# FAR_LR1_Remote_Recovery_Schematic_EasyED.net
KiCad netlist of a schematic drawn in EasyEDA
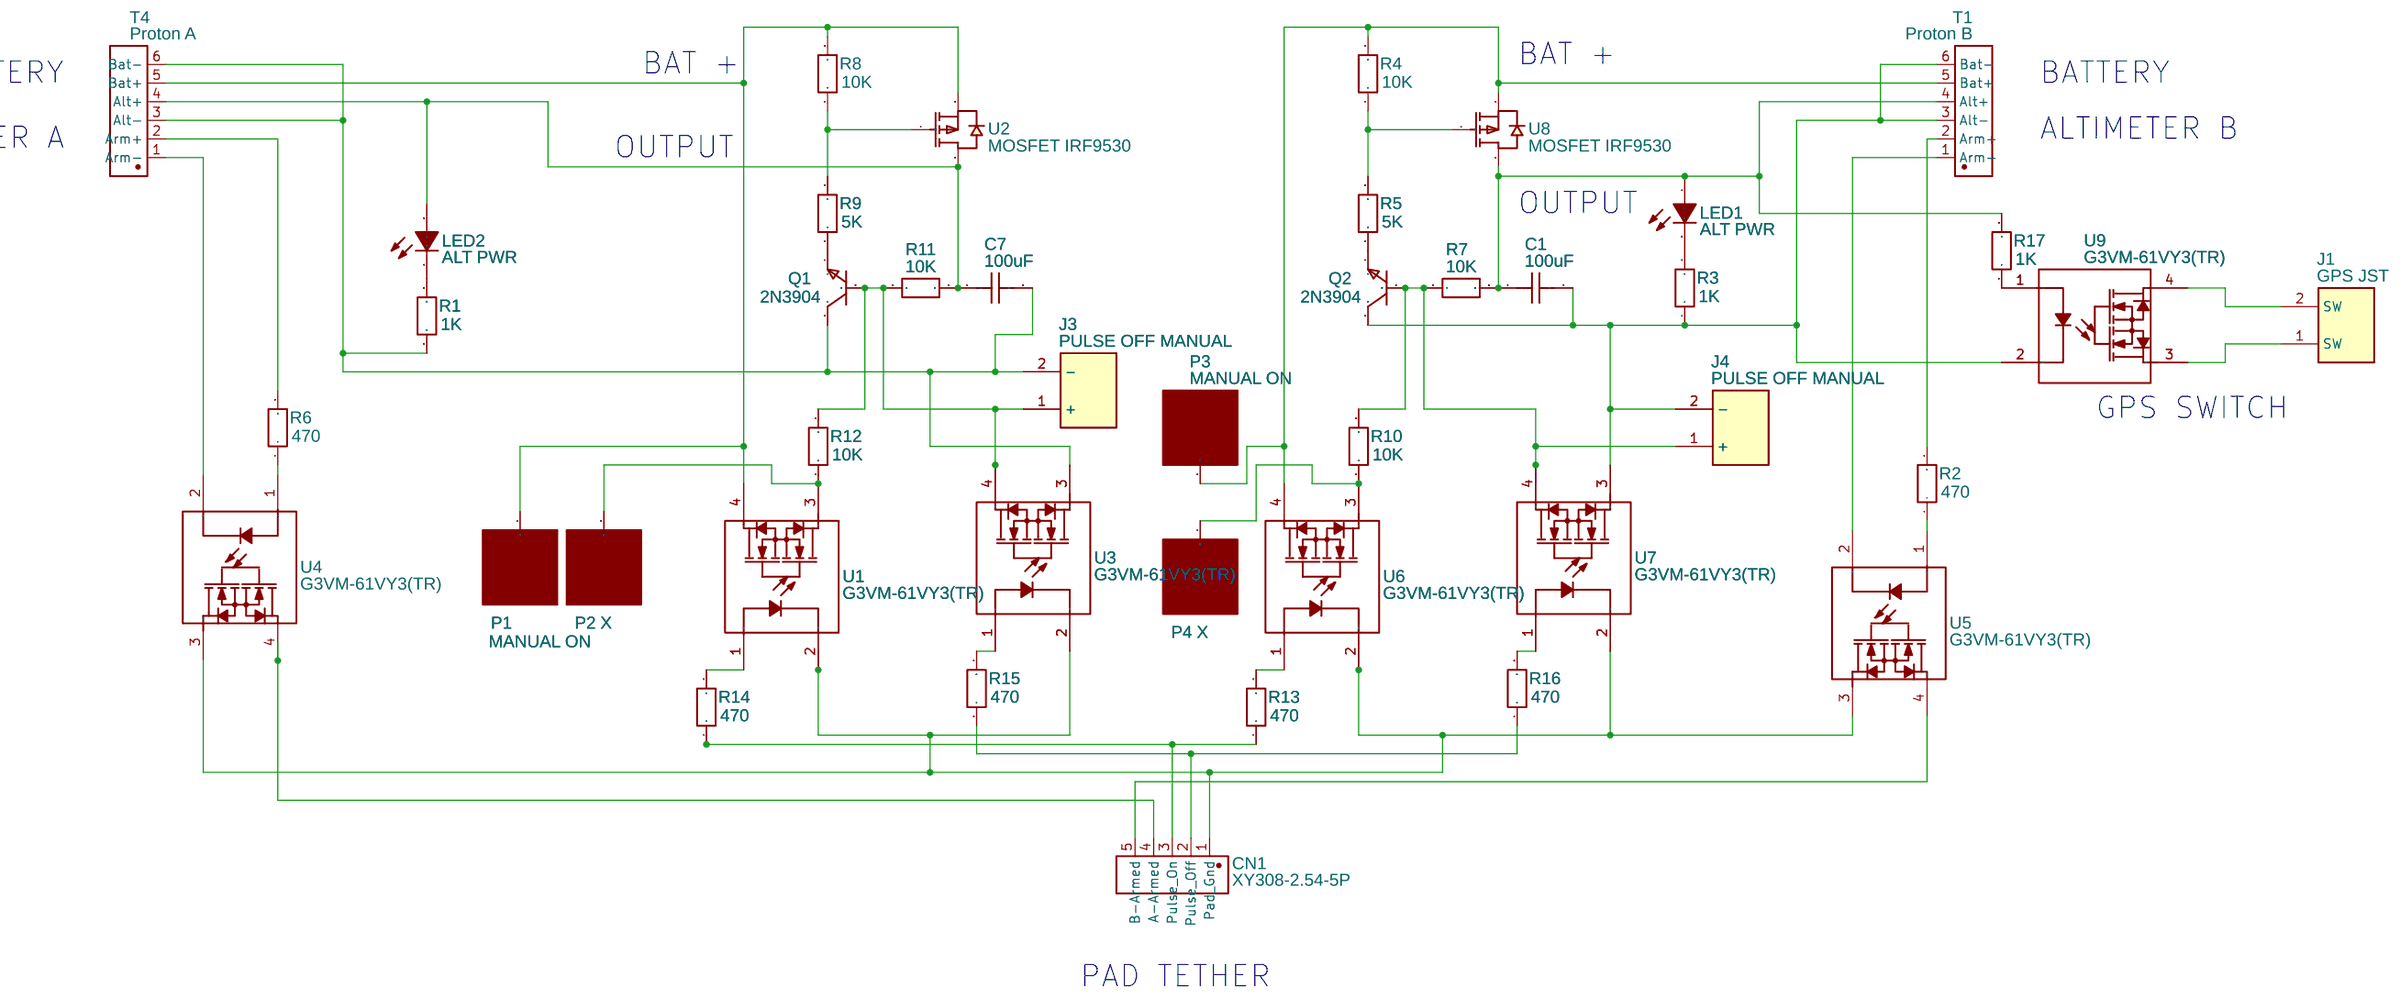
[diagram p0: schematic sheet]

(export (version "E")
  (design (tool "Eeschema 10.0.6"))
  (components
    (comp (ref "C1")
      (value "100uF")
      (fields
        (field (name "Manufacturer Part") "GRM31CR61A107MEA8L")
        (field (name "Manufacturer") "muRata(村田)")
      )
      (libsource (lib "") (part "GRM31CR61A107MEA8L"))
    )
    (comp (ref "C7")
      (value "100uF")
      (fields
        (field (name "Manufacturer Part") "GRM31CR61A107MEA8L")
        (field (name "Manufacturer") "muRata(村田)")
      )
      (libsource (lib "") (part "GRM31CR61A107MEA8L"))
    )
    (comp (ref "CN1")
      (value "XY308-2.54-5P")
      (fields (field (name "Manufacturer") "XINLAIYA(新莱亚)"))
      (libsource (lib "") (part "XY308-2.54-5P"))
    )
    (comp (ref "J1")
      (value "GPS JST")
      (fields (field (name "Manufacturer Part") "B2B-PH-K-S(LF)(SN)") (field (name "Manufacturer") "JST"))
      (libsource (lib "") (part "B2B-PH-K-S(LF)(SN)_1"))
    )
    (comp (ref "J3")
      (value "PULSE OFF MANUAL")
      (fields (field (name "Manufacturer Part") "B2B-PH-K-S(LF)(SN)") (field (name "Manufacturer") "JST"))
      (libsource (lib "") (part "B2B-PH-K-S(LF)(SN)"))
    )
    (comp (ref "J4")
      (value "PULSE OFF MANUAL")
      (fields (field (name "Manufacturer Part") "B2B-PH-K-S(LF)(SN)") (field (name "Manufacturer") "JST"))
      (libsource (lib "") (part "B2B-PH-K-S(LF)(SN)"))
    )
    (comp (ref "LED1")
      (value "ALT PWR")
      (fields
        (field (name "Manufacturer Part") "67-21/R6C-FN2Q1BZ/2T")
        (field (name "Manufacturer") "EVERLIGHT")
      )
      (libsource (lib "") (part "67-21/R6C-FN2Q1BZ/2T"))
    )
    (comp (ref "LED2")
      (value "ALT PWR")
      (fields
        (field (name "Manufacturer Part") "67-21/R6C-FN2Q1BZ/2T")
        (field (name "Manufacturer") "EVERLIGHT")
      )
      (libsource (lib "") (part "67-21/R6C-FN2Q1BZ/2T"))
    )
    (comp (ref "P1")
      (value "MANUAL ON")
      (fields (field (name "Manufacturer Part") "Soldering pad"))
      (libsource (lib "") (part "Solder Pad"))
    )
    (comp (ref "P2")
      (value "X")
      (fields (field (name "Manufacturer Part") "Soldering pad"))
      (libsource (lib "") (part "Solder Pad"))
    )
    (comp (ref "P3")
      (value "MANUAL ON")
      (fields (field (name "Manufacturer Part") "Soldering pad"))
      (libsource (lib "") (part "Solder Pad_1"))
    )
    (comp (ref "P4")
      (value "X")
      (fields (field (name "Manufacturer Part") "Soldering pad"))
      (libsource (lib "") (part "Solder Pad"))
    )
    (comp (ref "Q1")
      (value "2N3904")
      (fields (field (name "Manufacturer") "JSMSEMI(杰盛微)"))
      (libsource (lib "") (part "2N3904_C2874602"))
    )
    (comp (ref "Q2")
      (value "2N3904")
      (fields (field (name "Manufacturer") "JSMSEMI(杰盛微)"))
      (libsource (lib "") (part "2N3904_C2874602"))
    )
    (comp (ref "R1")
      (value "1K")
      (fields (field (name "Manufacturer Part") "SFR03EZPF1001") (field (name "Manufacturer") "ROHM(罗姆)"))
      (libsource (lib "") (part "SFR03EZPF1001"))
    )
    (comp (ref "R2")
      (value "470")
      (fields (field (name "Manufacturer Part") "SFR03EZPF1001") (field (name "Manufacturer") "ROHM(罗姆)"))
      (libsource (lib "") (part "SFR03EZPF1001"))
    )
    (comp (ref "R3")
      (value "1K")
      (fields (field (name "Manufacturer Part") "SFR03EZPF1001") (field (name "Manufacturer") "ROHM(罗姆)"))
      (libsource (lib "") (part "SFR03EZPF1001"))
    )
    (comp (ref "R4")
      (value "10K")
      (fields (field (name "Manufacturer Part") "SFR03EZPF1001") (field (name "Manufacturer") "ROHM(罗姆)"))
      (libsource (lib "") (part "SFR03EZPF1001"))
    )
    (comp (ref "R5")
      (value "5K")
      (fields (field (name "Manufacturer Part") "SFR03EZPF1001") (field (name "Manufacturer") "ROHM(罗姆)"))
      (libsource (lib "") (part "SFR03EZPF1001"))
    )
    (comp (ref "R6")
      (value "470")
      (fields (field (name "Manufacturer Part") "SFR03EZPF1001") (field (name "Manufacturer") "ROHM(罗姆)"))
      (libsource (lib "") (part "SFR03EZPF1001"))
    )
    (comp (ref "R7")
      (value "10K")
      (fields (field (name "Manufacturer Part") "SFR03EZPF1001") (field (name "Manufacturer") "ROHM(罗姆)"))
      (libsource (lib "") (part "SFR03EZPF1001_1"))
    )
    (comp (ref "R8")
      (value "10K")
      (fields (field (name "Manufacturer Part") "SFR03EZPF1001") (field (name "Manufacturer") "ROHM(罗姆)"))
      (libsource (lib "") (part "SFR03EZPF1001"))
    )
    (comp (ref "R9")
      (value "5K")
      (fields (field (name "Manufacturer Part") "SFR03EZPF1001") (field (name "Manufacturer") "ROHM(罗姆)"))
      (libsource (lib "") (part "SFR03EZPF1001"))
    )
    (comp (ref "R10")
      (value "10K")
      (fields (field (name "Manufacturer Part") "SFR03EZPF1001") (field (name "Manufacturer") "ROHM(罗姆)"))
      (libsource (lib "") (part "SFR03EZPF1001"))
    )
    (comp (ref "R11")
      (value "10K")
      (fields (field (name "Manufacturer Part") "SFR03EZPF1001") (field (name "Manufacturer") "ROHM(罗姆)"))
      (libsource (lib "") (part "SFR03EZPF1001_1"))
    )
    (comp (ref "R12")
      (value "10K")
      (fields (field (name "Manufacturer Part") "SFR03EZPF1001") (field (name "Manufacturer") "ROHM(罗姆)"))
      (libsource (lib "") (part "SFR03EZPF1001"))
    )
    (comp (ref "R13")
      (value "470")
      (fields (field (name "Manufacturer Part") "SFR03EZPF1001") (field (name "Manufacturer") "ROHM(罗姆)"))
      (libsource (lib "") (part "SFR03EZPF1001"))
    )
    (comp (ref "R14")
      (value "470")
      (fields (field (name "Manufacturer Part") "SFR03EZPF1001") (field (name "Manufacturer") "ROHM(罗姆)"))
      (libsource (lib "") (part "SFR03EZPF1001"))
    )
    (comp (ref "R15")
      (value "470")
      (fields (field (name "Manufacturer Part") "SFR03EZPF1001") (field (name "Manufacturer") "ROHM(罗姆)"))
      (libsource (lib "") (part "SFR03EZPF1001"))
    )
    (comp (ref "R16")
      (value "470")
      (fields (field (name "Manufacturer Part") "SFR03EZPF1001") (field (name "Manufacturer") "ROHM(罗姆)"))
      (libsource (lib "") (part "SFR03EZPF1001"))
    )
    (comp (ref "R17")
      (value "1K")
      (fields (field (name "Manufacturer Part") "SFR03EZPF1001") (field (name "Manufacturer") "ROHM(罗姆)"))
      (libsource (lib "") (part "SFR03EZPF1001"))
    )
    (comp (ref "T1")
      (value "Proton B")
      (fields
        (field (name "Manufacturer Part") "DB125-2.54-6P-GN")
        (field (name "Manufacturer") "DIBO(地博电子)")
      )
      (libsource (lib "") (part "DB125-2.54-6P-GN"))
    )
    (comp (ref "T4")
      (value "Proton A")
      (fields
        (field (name "Manufacturer Part") "DB125-2.54-6P-GN")
        (field (name "Manufacturer") "DIBO(地博电子)")
      )
      (libsource (lib "") (part "DB125-2.54-6P-GN_1"))
    )
    (comp (ref "U1")
      (value "G3VM-61VY3(TR)")
      (fields (field (name "Manufacturer") "OMRON(欧姆龙)"))
      (libsource (lib "") (part "G3VM-61VY3(TR)_1"))
    )
    (comp (ref "U2")
      (value "MOSFET IRF9530")
      (fields (field (name "Manufacturer Part") "IRF9530PBF-BE3") (field (name "Manufacturer") "VISHAY(威世)"))
      (libsource (lib "") (part "IRF9530PBF-BE3"))
    )
    (comp (ref "U3")
      (value "G3VM-61VY3(TR)")
      (fields (field (name "Manufacturer") "OMRON(欧姆龙)"))
      (libsource (lib "") (part "G3VM-61VY3(TR)_1"))
    )
    (comp (ref "U4")
      (value "G3VM-61VY3(TR)")
      (fields (field (name "Manufacturer") "OMRON(欧姆龙)"))
      (libsource (lib "") (part "G3VM-61VY3(TR)"))
    )
    (comp (ref "U5")
      (value "G3VM-61VY3(TR)")
      (fields (field (name "Manufacturer") "OMRON(欧姆龙)"))
      (libsource (lib "") (part "G3VM-61VY3(TR)"))
    )
    (comp (ref "U6")
      (value "G3VM-61VY3(TR)")
      (fields (field (name "Manufacturer") "OMRON(欧姆龙)"))
      (libsource (lib "") (part "G3VM-61VY3(TR)_1"))
    )
    (comp (ref "U7")
      (value "G3VM-61VY3(TR)")
      (fields (field (name "Manufacturer") "OMRON(欧姆龙)"))
      (libsource (lib "") (part "G3VM-61VY3(TR)_1"))
    )
    (comp (ref "U8")
      (value "MOSFET IRF9530")
      (fields (field (name "Manufacturer Part") "IRF9530PBF-BE3") (field (name "Manufacturer") "VISHAY(威世)"))
      (libsource (lib "") (part "IRF9530PBF-BE3"))
    )
    (comp (ref "U9")
      (value "G3VM-61VY3(TR)")
      (fields (field (name "Manufacturer") "OMRON(欧姆龙)"))
      (libsource (lib "") (part "G3VM-61VY3(TR)_2"))
    )
  )
  (nets
    (net (code "1") (name "Net-(CN1-A-Armed)") (class "Default")
      (node (ref "CN1") (pin "4") (pinfunction "A-Armed_4") (pintype "unspecified"))
      (node (ref "U4") (pin "4") (pinfunction "4_4") (pintype "unspecified"))
    )
    (net (code "2") (name "Net-(CN1-B-Armed)") (class "Default")
      (node (ref "CN1") (pin "5") (pinfunction "B-Armed_5") (pintype "unspecified"))
      (node (ref "U5") (pin "4") (pinfunction "4_4") (pintype "unspecified"))
    )
    (net (code "3") (name "Net-(CN1-Pad_Gnd)") (class "Default")
      (node (ref "CN1") (pin "1") (pinfunction "Pad_Gnd_1") (pintype "unspecified"))
      (node (ref "U1") (pin "2") (pinfunction "2_2") (pintype "unspecified"))
      (node (ref "U3") (pin "2") (pinfunction "2_2") (pintype "unspecified"))
      (node (ref "U4") (pin "3") (pinfunction "3_3") (pintype "unspecified"))
      (node (ref "U5") (pin "3") (pinfunction "3_3") (pintype "unspecified"))
      (node (ref "U6") (pin "2") (pinfunction "2_2") (pintype "unspecified"))
      (node (ref "U7") (pin "2") (pinfunction "2_2") (pintype "unspecified"))
    )
    (net (code "4") (name "Net-(CN1-Pulse_Off)") (class "Default")
      (node (ref "CN1") (pin "2") (pinfunction "Pulse_Off_2") (pintype "unspecified"))
      (node (ref "R15") (pin "1") (pinfunction "1_1") (pintype "unspecified"))
      (node (ref "R16") (pin "1") (pinfunction "1_1") (pintype "unspecified"))
    )
    (net (code "5") (name "Net-(CN1-Pulse_On)") (class "Default")
      (node (ref "CN1") (pin "3") (pinfunction "Pulse_On_3") (pintype "unspecified"))
      (node (ref "R13") (pin "1") (pinfunction "1_1") (pintype "unspecified"))
      (node (ref "R14") (pin "1") (pinfunction "1_1") (pintype "unspecified"))
    )
    (net (code "6") (name "Net-(J1-SW-Pad1)") (class "Default")
      (node (ref "J1") (pin "1") (pinfunction "SW_1") (pintype "input"))
      (node (ref "U9") (pin "3") (pinfunction "3_3") (pintype "unspecified"))
    )
    (net (code "7") (name "Net-(J1-SW-Pad2)") (class "Default")
      (node (ref "J1") (pin "2") (pinfunction "SW_2") (pintype "input"))
      (node (ref "U9") (pin "4") (pinfunction "4_4") (pintype "unspecified"))
    )
    (net (code "8") (name "Net-(J3-+)") (class "Default")
      (node (ref "J3") (pin "1") (pinfunction "+_1") (pintype "input"))
      (node (ref "Q1") (pin "2") (pinfunction "B_2") (pintype "unspecified"))
      (node (ref "R11") (pin "1") (pinfunction "1_1") (pintype "unspecified"))
      (node (ref "R12") (pin "2") (pinfunction "2_2") (pintype "unspecified"))
      (node (ref "U3") (pin "4") (pinfunction "4_4") (pintype "unspecified"))
    )
    (net (code "9") (name "Net-(J3--)") (class "Default")
      (node (ref "C7") (pin "2") (pinfunction "2_2") (pintype "unspecified"))
      (node (ref "J3") (pin "2") (pinfunction "-_2") (pintype "input"))
      (node (ref "Q1") (pin "3") (pinfunction "C_3") (pintype "unspecified"))
      (node (ref "R1") (pin "1") (pinfunction "1_1") (pintype "unspecified"))
      (node (ref "T4") (pin "3") (pinfunction "Alt-_3") (pintype "unspecified"))
      (node (ref "T4") (pin "6") (pinfunction "Bat-_6") (pintype "unspecified"))
      (node (ref "U3") (pin "3") (pinfunction "3_3") (pintype "unspecified"))
    )
    (net (code "10") (name "Net-(J4-+)") (class "Default")
      (node (ref "J4") (pin "1") (pinfunction "+_1") (pintype "input"))
      (node (ref "Q2") (pin "2") (pinfunction "B_2") (pintype "unspecified"))
      (node (ref "R10") (pin "2") (pinfunction "2_2") (pintype "unspecified"))
      (node (ref "R7") (pin "1") (pinfunction "1_1") (pintype "unspecified"))
      (node (ref "U7") (pin "4") (pinfunction "4_4") (pintype "unspecified"))
    )
    (net (code "11") (name "Net-(J4--)") (class "Default")
      (node (ref "C1") (pin "2") (pinfunction "2_2") (pintype "unspecified"))
      (node (ref "J4") (pin "2") (pinfunction "-_2") (pintype "input"))
      (node (ref "Q2") (pin "3") (pinfunction "C_3") (pintype "unspecified"))
      (node (ref "R3") (pin "1") (pinfunction "1_1") (pintype "unspecified"))
      (node (ref "T1") (pin "3") (pinfunction "Alt-_3") (pintype "unspecified"))
      (node (ref "T1") (pin "6") (pinfunction "Bat-_6") (pintype "unspecified"))
      (node (ref "U7") (pin "3") (pinfunction "3_3") (pintype "unspecified"))
      (node (ref "U9") (pin "2") (pinfunction "2_2") (pintype "unspecified"))
    )
    (net (code "12") (name "Net-(LED1-A)") (class "Default")
      (node (ref "C1") (pin "1") (pinfunction "1_1") (pintype "unspecified"))
      (node (ref "LED1") (pin "1") (pinfunction "A_1") (pintype "input"))
      (node (ref "R17") (pin "2") (pinfunction "2_2") (pintype "unspecified"))
      (node (ref "R7") (pin "2") (pinfunction "2_2") (pintype "unspecified"))
      (node (ref "T1") (pin "4") (pinfunction "Alt+_4") (pintype "unspecified"))
      (node (ref "U8") (pin "2") (pinfunction "D_2") (pintype "unspecified"))
    )
    (net (code "13") (name "Net-(LED1-C)") (class "Default")
      (node (ref "LED1") (pin "2") (pinfunction "C_2") (pintype "input"))
      (node (ref "R3") (pin "2") (pinfunction "2_2") (pintype "unspecified"))
    )
    (net (code "14") (name "Net-(LED2-A)") (class "Default")
      (node (ref "C7") (pin "1") (pinfunction "1_1") (pintype "unspecified"))
      (node (ref "LED2") (pin "1") (pinfunction "A_1") (pintype "input"))
      (node (ref "R11") (pin "2") (pinfunction "2_2") (pintype "unspecified"))
      (node (ref "T4") (pin "4") (pinfunction "Alt+_4") (pintype "unspecified"))
      (node (ref "U2") (pin "2") (pinfunction "D_2") (pintype "unspecified"))
    )
    (net (code "15") (name "Net-(LED2-C)") (class "Default")
      (node (ref "LED2") (pin "2") (pinfunction "C_2") (pintype "input"))
      (node (ref "R1") (pin "2") (pinfunction "2_2") (pintype "unspecified"))
    )
    (net (code "16") (name "Net-(P2-Pad1)") (class "Default")
      (node (ref "P2") (pin "1") (pinfunction "1_1") (pintype "unspecified"))
      (node (ref "R12") (pin "1") (pinfunction "1_1") (pintype "unspecified"))
      (node (ref "U1") (pin "3") (pinfunction "3_3") (pintype "unspecified"))
    )
    (net (code "17") (name "Net-(P4-Pad1)") (class "Default")
      (node (ref "P4") (pin "1") (pinfunction "1_1") (pintype "unspecified"))
      (node (ref "R10") (pin "1") (pinfunction "1_1") (pintype "unspecified"))
      (node (ref "U6") (pin "3") (pinfunction "3_3") (pintype "unspecified"))
    )
    (net (code "18") (name "Net-(Q1-E)") (class "Default")
      (node (ref "Q1") (pin "1") (pinfunction "E_1") (pintype "unspecified"))
      (node (ref "R9") (pin "1") (pinfunction "1_1") (pintype "unspecified"))
    )
    (net (code "19") (name "Net-(Q2-E)") (class "Default")
      (node (ref "Q2") (pin "1") (pinfunction "E_1") (pintype "unspecified"))
      (node (ref "R5") (pin "1") (pinfunction "1_1") (pintype "unspecified"))
    )
    (net (code "20") (name "Net-(R2-Pad1)") (class "Default")
      (node (ref "R2") (pin "1") (pinfunction "1_1") (pintype "unspecified"))
      (node (ref "U5") (pin "1") (pinfunction "1_1") (pintype "unspecified"))
    )
    (net (code "21") (name "Net-(R6-Pad1)") (class "Default")
      (node (ref "R6") (pin "1") (pinfunction "1_1") (pintype "unspecified"))
      (node (ref "U4") (pin "1") (pinfunction "1_1") (pintype "unspecified"))
    )
    (net (code "22") (name "Net-(R13-Pad2)") (class "Default")
      (node (ref "R13") (pin "2") (pinfunction "2_2") (pintype "unspecified"))
      (node (ref "U6") (pin "1") (pinfunction "1_1") (pintype "unspecified"))
    )
    (net (code "23") (name "Net-(R14-Pad2)") (class "Default")
      (node (ref "R14") (pin "2") (pinfunction "2_2") (pintype "unspecified"))
      (node (ref "U1") (pin "1") (pinfunction "1_1") (pintype "unspecified"))
    )
    (net (code "24") (name "Net-(R15-Pad2)") (class "Default")
      (node (ref "R15") (pin "2") (pinfunction "2_2") (pintype "unspecified"))
      (node (ref "U3") (pin "1") (pinfunction "1_1") (pintype "unspecified"))
    )
    (net (code "25") (name "Net-(R16-Pad2)") (class "Default")
      (node (ref "R16") (pin "2") (pinfunction "2_2") (pintype "unspecified"))
      (node (ref "U7") (pin "1") (pinfunction "1_1") (pintype "unspecified"))
    )
    (net (code "26") (name "Net-(R17-Pad1)") (class "Default")
      (node (ref "R17") (pin "1") (pinfunction "1_1") (pintype "unspecified"))
      (node (ref "U9") (pin "1") (pinfunction "1_1") (pintype "unspecified"))
    )
    (net (code "27") (name "Net-(T1-Arm+)") (class "Default")
      (node (ref "R2") (pin "2") (pinfunction "2_2") (pintype "unspecified"))
      (node (ref "T1") (pin "2") (pinfunction "Arm+_2") (pintype "unspecified"))
    )
    (net (code "28") (name "Net-(T1-Arm-)") (class "Default")
      (node (ref "T1") (pin "1") (pinfunction "Arm-_1") (pintype "unspecified"))
      (node (ref "U5") (pin "2") (pinfunction "2_2") (pintype "unspecified"))
    )
    (net (code "29") (name "Net-(T1-Bat+)") (class "Default")
      (node (ref "P3") (pin "1") (pinfunction "1_1") (pintype "unspecified"))
      (node (ref "R4") (pin "2") (pinfunction "2_2") (pintype "unspecified"))
      (node (ref "T1") (pin "5") (pinfunction "Bat+_5") (pintype "unspecified"))
      (node (ref "U6") (pin "4") (pinfunction "4_4") (pintype "unspecified"))
      (node (ref "U8") (pin "3") (pinfunction "S_3") (pintype "unspecified"))
    )
    (net (code "30") (name "Net-(T4-Arm+)") (class "Default")
      (node (ref "R6") (pin "2") (pinfunction "2_2") (pintype "unspecified"))
      (node (ref "T4") (pin "2") (pinfunction "Arm+_2") (pintype "unspecified"))
    )
    (net (code "31") (name "Net-(T4-Arm-)") (class "Default")
      (node (ref "T4") (pin "1") (pinfunction "Arm-_1") (pintype "unspecified"))
      (node (ref "U4") (pin "2") (pinfunction "2_2") (pintype "unspecified"))
    )
    (net (code "32") (name "Net-(T4-Bat+)") (class "Default")
      (node (ref "P1") (pin "1") (pinfunction "1_1") (pintype "unspecified"))
      (node (ref "R8") (pin "2") (pinfunction "2_2") (pintype "unspecified"))
      (node (ref "T4") (pin "5") (pinfunction "Bat+_5") (pintype "unspecified"))
      (node (ref "U1") (pin "4") (pinfunction "4_4") (pintype "unspecified"))
      (node (ref "U2") (pin "3") (pinfunction "S_3") (pintype "unspecified"))
    )
    (net (code "33") (name "Net-(U2-G)") (class "Default")
      (node (ref "R8") (pin "1") (pinfunction "1_1") (pintype "unspecified"))
      (node (ref "R9") (pin "2") (pinfunction "2_2") (pintype "unspecified"))
      (node (ref "U2") (pin "1") (pinfunction "G_1") (pintype "unspecified"))
    )
    (net (code "34") (name "Net-(U8-G)") (class "Default")
      (node (ref "R4") (pin "1") (pinfunction "1_1") (pintype "unspecified"))
      (node (ref "R5") (pin "2") (pinfunction "2_2") (pintype "unspecified"))
      (node (ref "U8") (pin "1") (pinfunction "G_1") (pintype "unspecified"))
    )
  )
)
